# 3_peripherals.net
KiCad netlist of a schematic drawn in Altium Designer
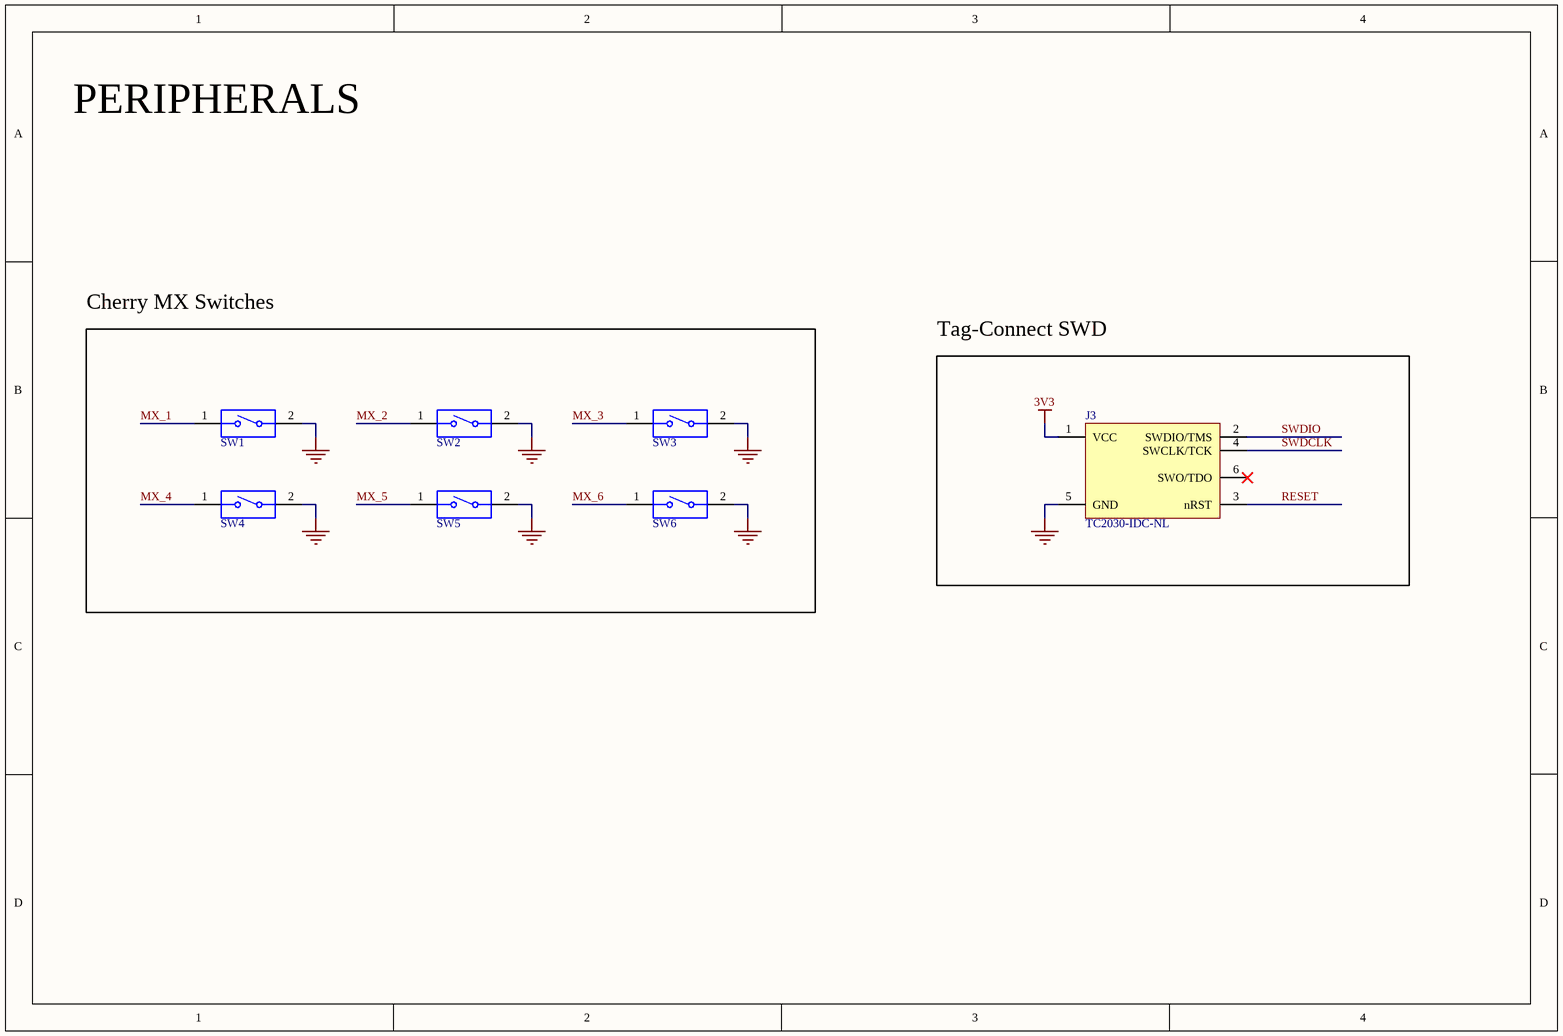
[diagram p0: 3_peripherals.SchDoc]

(export (version "E")
  (design (tool "Eeschema 10.0.6"))
  (components
    (comp (ref "J3")
      (value "TC2030-IDC-NL")
      (footprint "TAG_TC2030-IDC-NL")
      (description "CABLE ADAPTER 6 POS")
      (libsource (lib "University of South Florida") (part "TC2030-IDC-NL"))
    )
    (comp (ref "SW1")
      (value "MX1A-11NW")
      (footprint "CHRY-MX1A-11NW_V")
      (libsource (lib "University of South Florida") (part "KEYSW-SPST-2"))
    )
    (comp (ref "SW2")
      (value "MX1A-11NW")
      (footprint "CHRY-MX1A-11NW_V")
      (libsource (lib "University of South Florida") (part "KEYSW-SPST-2"))
    )
    (comp (ref "SW3")
      (value "MX1A-11NW")
      (footprint "CHRY-MX1A-11NW_V")
      (libsource (lib "University of South Florida") (part "KEYSW-SPST-2"))
    )
    (comp (ref "SW4")
      (value "MX1A-11NW")
      (footprint "CHRY-MX1A-11NW_V")
      (libsource (lib "University of South Florida") (part "KEYSW-SPST-2"))
    )
    (comp (ref "SW5")
      (value "MX1A-11NW")
      (footprint "CHRY-MX1A-11NW_V")
      (libsource (lib "University of South Florida") (part "KEYSW-SPST-2"))
    )
    (comp (ref "SW6")
      (value "MX1A-11NW")
      (footprint "CHRY-MX1A-11NW_V")
      (libsource (lib "University of South Florida") (part "KEYSW-SPST-2"))
    )
  )
  (nets
    (net (code "1") (name "/MX_1") (class "Default")
      (node (ref "SW1") (pin "1") (pinfunction "1_1") (pintype "passive"))
    )
    (net (code "2") (name "/MX_2") (class "Default")
      (node (ref "SW2") (pin "1") (pinfunction "1_1") (pintype "passive"))
    )
    (net (code "3") (name "/MX_3") (class "Default")
      (node (ref "SW3") (pin "1") (pinfunction "1_1") (pintype "passive"))
    )
    (net (code "4") (name "/MX_4") (class "Default")
      (node (ref "SW4") (pin "1") (pinfunction "1_1") (pintype "passive"))
    )
    (net (code "5") (name "/MX_5") (class "Default")
      (node (ref "SW5") (pin "1") (pinfunction "1_1") (pintype "passive"))
    )
    (net (code "6") (name "/MX_6") (class "Default")
      (node (ref "SW6") (pin "1") (pinfunction "1_1") (pintype "passive"))
    )
    (net (code "7") (name "/RESET") (class "Default")
      (node (ref "J3") (pin "3") (pinfunction "nRST_3") (pintype "passive"))
    )
    (net (code "8") (name "/SWDCLK") (class "Default")
      (node (ref "J3") (pin "4") (pinfunction "SWCLK/TCK_4") (pintype "passive"))
    )
    (net (code "9") (name "/SWDIO") (class "Default")
      (node (ref "J3") (pin "2") (pinfunction "SWDIO/TMS_2") (pintype "passive"))
    )
    (net (code "10") (name "3V3") (class "Default")
      (node (ref "J3") (pin "1") (pinfunction "VCC_1") (pintype "passive"))
    )
    (net (code "11") (name "GND") (class "Default")
      (node (ref "J3") (pin "5") (pinfunction "GND_5") (pintype "passive"))
      (node (ref "SW1") (pin "2") (pinfunction "2_2") (pintype "passive"))
      (node (ref "SW2") (pin "2") (pinfunction "2_2") (pintype "passive"))
      (node (ref "SW3") (pin "2") (pinfunction "2_2") (pintype "passive"))
      (node (ref "SW4") (pin "2") (pinfunction "2_2") (pintype "passive"))
      (node (ref "SW5") (pin "2") (pinfunction "2_2") (pintype "passive"))
      (node (ref "SW6") (pin "2") (pinfunction "2_2") (pintype "passive"))
    )
    (net (code "12") (name "unconnected-(J3-SWO{slash}TDO-Pad6)") (class "Default")
      (node (ref "J3") (pin "6") (pinfunction "SWO/TDO_6") (pintype "passive+no_connect"))
    )
  )
)
